# CNCMicaMini.net
KiCad netlist of a schematic drawn in Altium Designer
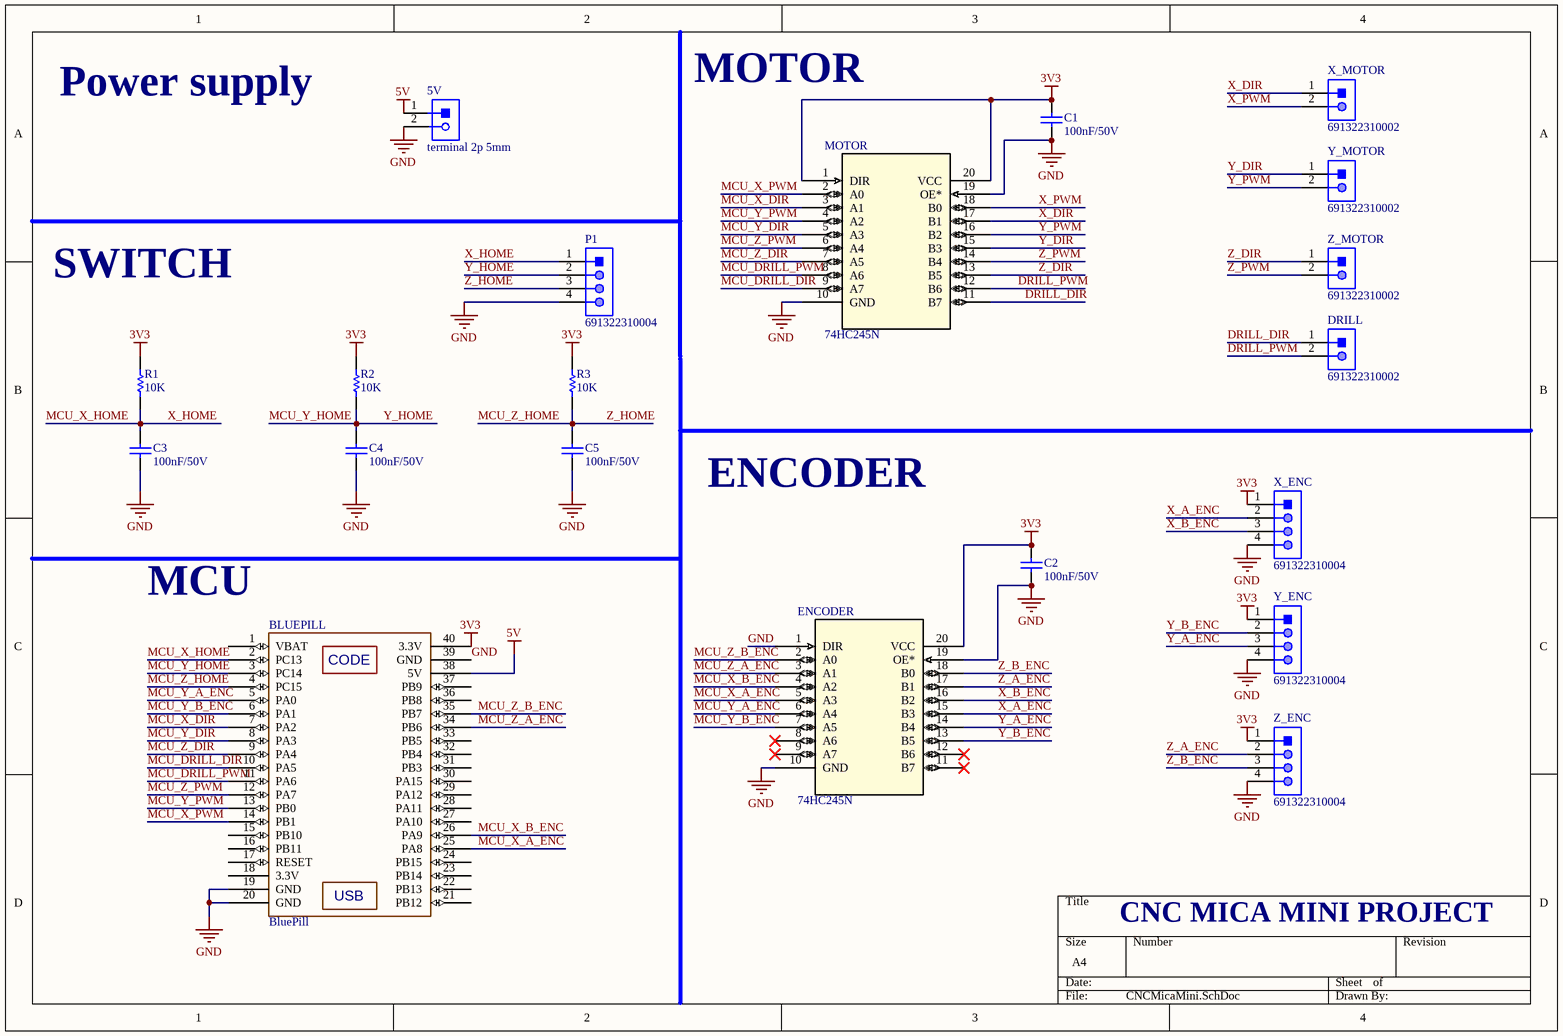
[diagram p0: CNCMicaMini.SchDoc]

(export (version "E")
  (design (tool "Eeschema 10.0.6"))
  (components
    (comp (ref "5V")
      (value "terminal 2p 5mm")
      (footprint "terminal 2p 5mm")
      (libsource (lib "CNCMicaMini") (part "terminal 2p 5mm"))
    )
    (comp (ref "BLUEPILL")
      (value "BluePill")
      (footprint "BlUEPILL")
      (libsource (lib "dev-board") (part "BluePill"))
    )
    (comp (ref "C1")
      (value "100nF/50V")
      (footprint "CAP-SM-0805")
      (description "CAP CER 0.1UF 50V Y5V 0805")
      (fields
        (field (name "MANUFACTURER") "Samsung Electro-Mechanics")
        (field (name "MANUFACTURER PART NUMBER") "CL21F104ZBCNNNC")
      )
      (libsource (lib "capacitor-smd") (part "Cap-100nF-50V-0805"))
    )
    (comp (ref "C2")
      (value "100nF/50V")
      (footprint "CAP-SM-0805")
      (description "CAP CER 0.1UF 50V Y5V 0805")
      (fields
        (field (name "MANUFACTURER") "Samsung Electro-Mechanics")
        (field (name "MANUFACTURER PART NUMBER") "CL21F104ZBCNNNC")
      )
      (libsource (lib "capacitor-smd") (part "Cap-100nF-50V-0805"))
    )
    (comp (ref "C3")
      (value "100nF/50V")
      (footprint "CAP-SM-0805")
      (description "CAP CER 0.1UF 50V Y5V 0805")
      (fields
        (field (name "MANUFACTURER") "Samsung Electro-Mechanics")
        (field (name "MANUFACTURER PART NUMBER") "CL21F104ZBCNNNC")
      )
      (libsource (lib "capacitor-smd") (part "Cap-100nF-50V-0805"))
    )
    (comp (ref "C4")
      (value "100nF/50V")
      (footprint "CAP-SM-0805")
      (description "CAP CER 0.1UF 50V Y5V 0805")
      (fields
        (field (name "MANUFACTURER") "Samsung Electro-Mechanics")
        (field (name "MANUFACTURER PART NUMBER") "CL21F104ZBCNNNC")
      )
      (libsource (lib "capacitor-smd") (part "Cap-100nF-50V-0805"))
    )
    (comp (ref "C5")
      (value "100nF/50V")
      (footprint "CAP-SM-0805")
      (description "CAP CER 0.1UF 50V Y5V 0805")
      (fields
        (field (name "MANUFACTURER") "Samsung Electro-Mechanics")
        (field (name "MANUFACTURER PART NUMBER") "CL21F104ZBCNNNC")
      )
      (libsource (lib "capacitor-smd") (part "Cap-100nF-50V-0805"))
    )
    (comp (ref "DRILL")
      (value "691322310002")
      (footprint "691322310002")
      (description "WR-TBL Serie 322 Horizontal PCB Header, Pluggable, pitch 3.81mm, 2p")
      (fields (field (name "PUBLISHER") "Wurth Elektronik"))
      (libsource (lib "WR-TBL_Pluggable PCB Header") (part "691322310002"))
    )
    (comp (ref "ENCODER")
      (value "74HC245N")
      (footprint "74HC245N")
      (description "No Description Available")
      (fields (field (name "COPYRIGHT") "Copyright (C) 2022 Ultra Librarian. All rights reserved."))
      (libsource (lib "CNCMicaMini") (part "74HC245N"))
    )
    (comp (ref "MOTOR")
      (value "74HC245N")
      (footprint "74HC245N")
      (description "No Description Available")
      (fields (field (name "COPYRIGHT") "Copyright (C) 2022 Ultra Librarian. All rights reserved."))
      (libsource (lib "CNCMicaMini") (part "74HC245N"))
    )
    (comp (ref "P1")
      (value "691322310004")
      (footprint "691322310004")
      (description "WR-TBL Serie 322 Horizontal PCB Header, Pluggable, pitch 3.81mm, 4p")
      (fields (field (name "PUBLISHER") "Wurth Elektronik"))
      (libsource (lib "WR-TBL_Pluggable PCB Header") (part "691322310004"))
    )
    (comp (ref "R1")
      (value "10K")
      (footprint "resistor-smd:RES-SM-0805")
      (description "RES 10K OHM 1% 1/4W 0805")
      (fields
        (field (name "MANUFACTURER") "Stackpole Electronics Inc")
        (field (name "MANUFACTURER PART NUMBER") "RNCP0805FTD10K0")
      )
      (libsource (lib "resistor-smd") (part "Res-10k-0805"))
    )
    (comp (ref "R2")
      (value "10K")
      (footprint "resistor-smd:RES-SM-0805")
      (description "RES 10K OHM 1% 1/4W 0805")
      (fields
        (field (name "MANUFACTURER") "Stackpole Electronics Inc")
        (field (name "MANUFACTURER PART NUMBER") "RNCP0805FTD10K0")
      )
      (libsource (lib "resistor-smd") (part "Res-10k-0805"))
    )
    (comp (ref "R3")
      (value "10K")
      (footprint "resistor-smd:RES-SM-0805")
      (description "RES 10K OHM 1% 1/4W 0805")
      (fields
        (field (name "MANUFACTURER") "Stackpole Electronics Inc")
        (field (name "MANUFACTURER PART NUMBER") "RNCP0805FTD10K0")
      )
      (libsource (lib "resistor-smd") (part "Res-10k-0805"))
    )
    (comp (ref "X_ENC")
      (value "691322310004")
      (footprint "691322310004")
      (description "WR-TBL Serie 322 Horizontal PCB Header, Pluggable, pitch 3.81mm, 4p")
      (fields (field (name "PUBLISHER") "Wurth Elektronik"))
      (libsource (lib "WR-TBL_Pluggable PCB Header") (part "691322310004"))
    )
    (comp (ref "X_MOTOR")
      (value "691322310002")
      (footprint "691322310002")
      (description "WR-TBL Serie 322 Horizontal PCB Header, Pluggable, pitch 3.81mm, 2p")
      (fields (field (name "PUBLISHER") "Wurth Elektronik"))
      (libsource (lib "WR-TBL_Pluggable PCB Header") (part "691322310002"))
    )
    (comp (ref "Y_ENC")
      (value "691322310004")
      (footprint "691322310004")
      (description "WR-TBL Serie 322 Horizontal PCB Header, Pluggable, pitch 3.81mm, 4p")
      (fields (field (name "PUBLISHER") "Wurth Elektronik"))
      (libsource (lib "WR-TBL_Pluggable PCB Header") (part "691322310004"))
    )
    (comp (ref "Y_MOTOR")
      (value "691322310002")
      (footprint "691322310002")
      (description "WR-TBL Serie 322 Horizontal PCB Header, Pluggable, pitch 3.81mm, 2p")
      (fields (field (name "PUBLISHER") "Wurth Elektronik"))
      (libsource (lib "WR-TBL_Pluggable PCB Header") (part "691322310002"))
    )
    (comp (ref "Z_ENC")
      (value "691322310004")
      (footprint "691322310004")
      (description "WR-TBL Serie 322 Horizontal PCB Header, Pluggable, pitch 3.81mm, 4p")
      (fields (field (name "PUBLISHER") "Wurth Elektronik"))
      (libsource (lib "WR-TBL_Pluggable PCB Header") (part "691322310004"))
    )
    (comp (ref "Z_MOTOR")
      (value "691322310002")
      (footprint "691322310002")
      (description "WR-TBL Serie 322 Horizontal PCB Header, Pluggable, pitch 3.81mm, 2p")
      (fields (field (name "PUBLISHER") "Wurth Elektronik"))
      (libsource (lib "WR-TBL_Pluggable PCB Header") (part "691322310002"))
    )
  )
  (nets
    (net (code "1") (name "/DRILL_DIR") (class "Default")
      (node (ref "DRILL") (pin "1") (pinfunction "1_1") (pintype "passive"))
      (node (ref "MOTOR") (pin "11") (pinfunction "B7_11") (pintype "bidirectional"))
    )
    (net (code "2") (name "/DRILL_PWM") (class "Default")
      (node (ref "DRILL") (pin "2") (pinfunction "2_2") (pintype "passive"))
      (node (ref "MOTOR") (pin "12") (pinfunction "B6_12") (pintype "bidirectional"))
    )
    (net (code "3") (name "/MCU_DRILL_DIR") (class "Default")
      (node (ref "BLUEPILL") (pin "10") (pinfunction "PA5_10") (pintype "bidirectional"))
      (node (ref "MOTOR") (pin "9") (pinfunction "A7_9") (pintype "bidirectional"))
    )
    (net (code "4") (name "/MCU_DRILL_PWM") (class "Default")
      (node (ref "BLUEPILL") (pin "11") (pinfunction "PA6_11") (pintype "bidirectional"))
      (node (ref "MOTOR") (pin "8") (pinfunction "A6_8") (pintype "bidirectional"))
    )
    (net (code "5") (name "/MCU_X_A_ENC") (class "Default")
      (node (ref "BLUEPILL") (pin "25") (pinfunction "PA8_25") (pintype "bidirectional"))
      (node (ref "ENCODER") (pin "5") (pinfunction "A3_5") (pintype "bidirectional"))
    )
    (net (code "6") (name "/MCU_X_B_ENC") (class "Default")
      (node (ref "BLUEPILL") (pin "26") (pinfunction "PA9_26") (pintype "bidirectional"))
      (node (ref "ENCODER") (pin "4") (pinfunction "A2_4") (pintype "bidirectional"))
    )
    (net (code "7") (name "/MCU_X_DIR") (class "Default")
      (node (ref "BLUEPILL") (pin "7") (pinfunction "PA2_7") (pintype "bidirectional"))
      (node (ref "MOTOR") (pin "3") (pinfunction "A1_3") (pintype "bidirectional"))
    )
    (net (code "8") (name "/MCU_X_HOME") (class "Default")
      (node (ref "BLUEPILL") (pin "2") (pinfunction "PC13_2") (pintype "bidirectional"))
      (node (ref "C3") (pin "2") (pinfunction "2_2") (pintype "passive"))
      (node (ref "P1") (pin "1") (pinfunction "1_1") (pintype "passive"))
      (node (ref "R1") (pin "1") (pinfunction "1_1") (pintype "passive"))
    )
    (net (code "9") (name "/MCU_X_PWM") (class "Default")
      (node (ref "BLUEPILL") (pin "14") (pinfunction "PB1_14") (pintype "bidirectional"))
      (node (ref "MOTOR") (pin "2") (pinfunction "A0_2") (pintype "bidirectional"))
    )
    (net (code "10") (name "/MCU_Y_A_ENC") (class "Default")
      (node (ref "BLUEPILL") (pin "5") (pinfunction "PA0_5") (pintype "bidirectional"))
      (node (ref "ENCODER") (pin "6") (pinfunction "A4_6") (pintype "bidirectional"))
    )
    (net (code "11") (name "/MCU_Y_B_ENC") (class "Default")
      (node (ref "BLUEPILL") (pin "6") (pinfunction "PA1_6") (pintype "bidirectional"))
      (node (ref "ENCODER") (pin "7") (pinfunction "A5_7") (pintype "bidirectional"))
    )
    (net (code "12") (name "/MCU_Y_DIR") (class "Default")
      (node (ref "BLUEPILL") (pin "8") (pinfunction "PA3_8") (pintype "bidirectional"))
      (node (ref "MOTOR") (pin "5") (pinfunction "A3_5") (pintype "bidirectional"))
    )
    (net (code "13") (name "/MCU_Y_HOME") (class "Default")
      (node (ref "BLUEPILL") (pin "3") (pinfunction "PC14_3") (pintype "bidirectional"))
      (node (ref "C4") (pin "2") (pinfunction "2_2") (pintype "passive"))
      (node (ref "P1") (pin "2") (pinfunction "2_2") (pintype "passive"))
      (node (ref "R2") (pin "1") (pinfunction "1_1") (pintype "passive"))
    )
    (net (code "14") (name "/MCU_Y_PWM") (class "Default")
      (node (ref "BLUEPILL") (pin "13") (pinfunction "PB0_13") (pintype "bidirectional"))
      (node (ref "MOTOR") (pin "4") (pinfunction "A2_4") (pintype "bidirectional"))
    )
    (net (code "15") (name "/MCU_Z_A_ENC") (class "Default")
      (node (ref "BLUEPILL") (pin "34") (pinfunction "PB6_34") (pintype "bidirectional"))
      (node (ref "ENCODER") (pin "3") (pinfunction "A1_3") (pintype "bidirectional"))
    )
    (net (code "16") (name "/MCU_Z_B_ENC") (class "Default")
      (node (ref "BLUEPILL") (pin "35") (pinfunction "PB7_35") (pintype "bidirectional"))
      (node (ref "ENCODER") (pin "2") (pinfunction "A0_2") (pintype "bidirectional"))
    )
    (net (code "17") (name "/MCU_Z_DIR") (class "Default")
      (node (ref "BLUEPILL") (pin "9") (pinfunction "PA4_9") (pintype "bidirectional"))
      (node (ref "MOTOR") (pin "7") (pinfunction "A5_7") (pintype "bidirectional"))
    )
    (net (code "18") (name "/MCU_Z_HOME") (class "Default")
      (node (ref "BLUEPILL") (pin "4") (pinfunction "PC15_4") (pintype "bidirectional"))
      (node (ref "C5") (pin "2") (pinfunction "2_2") (pintype "passive"))
      (node (ref "P1") (pin "3") (pinfunction "3_3") (pintype "passive"))
      (node (ref "R3") (pin "1") (pinfunction "1_1") (pintype "passive"))
    )
    (net (code "19") (name "/MCU_Z_PWM") (class "Default")
      (node (ref "BLUEPILL") (pin "12") (pinfunction "PA7_12") (pintype "bidirectional"))
      (node (ref "MOTOR") (pin "6") (pinfunction "A4_6") (pintype "bidirectional"))
    )
    (net (code "20") (name "/X_A_ENC") (class "Default")
      (node (ref "ENCODER") (pin "15") (pinfunction "B3_15") (pintype "bidirectional"))
      (node (ref "X_ENC") (pin "2") (pinfunction "2_2") (pintype "passive"))
    )
    (net (code "21") (name "/X_B_ENC") (class "Default")
      (node (ref "ENCODER") (pin "16") (pinfunction "B2_16") (pintype "bidirectional"))
      (node (ref "X_ENC") (pin "3") (pinfunction "3_3") (pintype "passive"))
    )
    (net (code "22") (name "/X_DIR") (class "Default")
      (node (ref "MOTOR") (pin "17") (pinfunction "B1_17") (pintype "bidirectional"))
      (node (ref "X_MOTOR") (pin "1") (pinfunction "1_1") (pintype "passive"))
    )
    (net (code "23") (name "/X_PWM") (class "Default")
      (node (ref "MOTOR") (pin "18") (pinfunction "B0_18") (pintype "bidirectional"))
      (node (ref "X_MOTOR") (pin "2") (pinfunction "2_2") (pintype "passive"))
    )
    (net (code "24") (name "/Y_A_ENC") (class "Default")
      (node (ref "ENCODER") (pin "14") (pinfunction "B4_14") (pintype "bidirectional"))
      (node (ref "Y_ENC") (pin "3") (pinfunction "3_3") (pintype "passive"))
    )
    (net (code "25") (name "/Y_B_ENC") (class "Default")
      (node (ref "ENCODER") (pin "13") (pinfunction "B5_13") (pintype "bidirectional"))
      (node (ref "Y_ENC") (pin "2") (pinfunction "2_2") (pintype "passive"))
    )
    (net (code "26") (name "/Y_DIR") (class "Default")
      (node (ref "MOTOR") (pin "15") (pinfunction "B3_15") (pintype "bidirectional"))
      (node (ref "Y_MOTOR") (pin "1") (pinfunction "1_1") (pintype "passive"))
    )
    (net (code "27") (name "/Y_PWM") (class "Default")
      (node (ref "MOTOR") (pin "16") (pinfunction "B2_16") (pintype "bidirectional"))
      (node (ref "Y_MOTOR") (pin "2") (pinfunction "2_2") (pintype "passive"))
    )
    (net (code "28") (name "/Z_A_ENC") (class "Default")
      (node (ref "ENCODER") (pin "17") (pinfunction "B1_17") (pintype "bidirectional"))
      (node (ref "Z_ENC") (pin "2") (pinfunction "2_2") (pintype "passive"))
    )
    (net (code "29") (name "/Z_B_ENC") (class "Default")
      (node (ref "ENCODER") (pin "18") (pinfunction "B0_18") (pintype "bidirectional"))
      (node (ref "Z_ENC") (pin "3") (pinfunction "3_3") (pintype "passive"))
    )
    (net (code "30") (name "/Z_DIR") (class "Default")
      (node (ref "MOTOR") (pin "13") (pinfunction "B5_13") (pintype "bidirectional"))
      (node (ref "Z_MOTOR") (pin "1") (pinfunction "1_1") (pintype "passive"))
    )
    (net (code "31") (name "/Z_PWM") (class "Default")
      (node (ref "MOTOR") (pin "14") (pinfunction "B4_14") (pintype "bidirectional"))
      (node (ref "Z_MOTOR") (pin "2") (pinfunction "2_2") (pintype "passive"))
    )
    (net (code "32") (name "3V3") (class "Default")
      (node (ref "BLUEPILL") (pin "40") (pinfunction "3.3V_40") (pintype "power_in"))
      (node (ref "C1") (pin "2") (pinfunction "2_2") (pintype "passive"))
      (node (ref "C2") (pin "2") (pinfunction "2_2") (pintype "passive"))
      (node (ref "ENCODER") (pin "20") (pinfunction "VCC_20") (pintype "power_in"))
      (node (ref "MOTOR") (pin "1") (pinfunction "DIR_1") (pintype "input"))
      (node (ref "MOTOR") (pin "20") (pinfunction "VCC_20") (pintype "power_in"))
      (node (ref "R1") (pin "2") (pinfunction "2_2") (pintype "passive"))
      (node (ref "R2") (pin "2") (pinfunction "2_2") (pintype "passive"))
      (node (ref "R3") (pin "2") (pinfunction "2_2") (pintype "passive"))
      (node (ref "X_ENC") (pin "1") (pinfunction "1_1") (pintype "passive"))
      (node (ref "Y_ENC") (pin "1") (pinfunction "1_1") (pintype "passive"))
      (node (ref "Z_ENC") (pin "1") (pinfunction "1_1") (pintype "passive"))
    )
    (net (code "33") (name "5V") (class "Default")
      (node (ref "5V") (pin "1") (pinfunction "1_1") (pintype "passive"))
      (node (ref "BLUEPILL") (pin "38") (pinfunction "5V_38") (pintype "power_in"))
    )
    (net (code "34") (name "GND") (class "Default")
      (node (ref "5V") (pin "2") (pinfunction "1_2") (pintype "passive"))
      (node (ref "BLUEPILL") (pin "19") (pinfunction "GND_19") (pintype "power_in"))
      (node (ref "BLUEPILL") (pin "20") (pinfunction "GND_20") (pintype "power_in"))
      (node (ref "BLUEPILL") (pin "39") (pinfunction "GND_39") (pintype "power_in"))
      (node (ref "C1") (pin "1") (pinfunction "1_1") (pintype "passive"))
      (node (ref "C2") (pin "1") (pinfunction "1_1") (pintype "passive"))
      (node (ref "C3") (pin "1") (pinfunction "1_1") (pintype "passive"))
      (node (ref "C4") (pin "1") (pinfunction "1_1") (pintype "passive"))
      (node (ref "C5") (pin "1") (pinfunction "1_1") (pintype "passive"))
      (node (ref "ENCODER") (pin "1") (pinfunction "DIR_1") (pintype "input"))
      (node (ref "ENCODER") (pin "10") (pinfunction "GND_10") (pintype "power_in"))
      (node (ref "ENCODER") (pin "19") (pinfunction "OE*_19") (pintype "input"))
      (node (ref "MOTOR") (pin "10") (pinfunction "GND_10") (pintype "power_in"))
      (node (ref "MOTOR") (pin "19") (pinfunction "OE*_19") (pintype "input"))
      (node (ref "P1") (pin "4") (pinfunction "4_4") (pintype "passive"))
      (node (ref "X_ENC") (pin "4") (pinfunction "4_4") (pintype "passive"))
      (node (ref "Y_ENC") (pin "4") (pinfunction "4_4") (pintype "passive"))
      (node (ref "Z_ENC") (pin "4") (pinfunction "4_4") (pintype "passive"))
    )
    (net (code "35") (name "unconnected-(BLUEPILL-3.3V-Pad18)") (class "Default")
      (node (ref "BLUEPILL") (pin "18") (pinfunction "3.3V_18") (pintype "power_in"))
    )
    (net (code "36") (name "unconnected-(BLUEPILL-PA10-Pad27)") (class "Default")
      (node (ref "BLUEPILL") (pin "27") (pinfunction "PA10_27") (pintype "bidirectional"))
    )
    (net (code "37") (name "unconnected-(BLUEPILL-PA11-Pad28)") (class "Default")
      (node (ref "BLUEPILL") (pin "28") (pinfunction "PA11_28") (pintype "bidirectional"))
    )
    (net (code "38") (name "unconnected-(BLUEPILL-PA12-Pad29)") (class "Default")
      (node (ref "BLUEPILL") (pin "29") (pinfunction "PA12_29") (pintype "bidirectional"))
    )
    (net (code "39") (name "unconnected-(BLUEPILL-PA15-Pad30)") (class "Default")
      (node (ref "BLUEPILL") (pin "30") (pinfunction "PA15_30") (pintype "bidirectional"))
    )
    (net (code "40") (name "unconnected-(BLUEPILL-PB3-Pad31)") (class "Default")
      (node (ref "BLUEPILL") (pin "31") (pinfunction "PB3_31") (pintype "bidirectional"))
    )
    (net (code "41") (name "unconnected-(BLUEPILL-PB4-Pad32)") (class "Default")
      (node (ref "BLUEPILL") (pin "32") (pinfunction "PB4_32") (pintype "bidirectional"))
    )
    (net (code "42") (name "unconnected-(BLUEPILL-PB5-Pad33)") (class "Default")
      (node (ref "BLUEPILL") (pin "33") (pinfunction "PB5_33") (pintype "bidirectional"))
    )
    (net (code "43") (name "unconnected-(BLUEPILL-PB8-Pad36)") (class "Default")
      (node (ref "BLUEPILL") (pin "36") (pinfunction "PB8_36") (pintype "bidirectional"))
    )
    (net (code "44") (name "unconnected-(BLUEPILL-PB9-Pad37)") (class "Default")
      (node (ref "BLUEPILL") (pin "37") (pinfunction "PB9_37") (pintype "bidirectional"))
    )
    (net (code "45") (name "unconnected-(BLUEPILL-PB10-Pad15)") (class "Default")
      (node (ref "BLUEPILL") (pin "15") (pinfunction "PB10_15") (pintype "bidirectional"))
    )
    (net (code "46") (name "unconnected-(BLUEPILL-PB11-Pad16)") (class "Default")
      (node (ref "BLUEPILL") (pin "16") (pinfunction "PB11_16") (pintype "bidirectional"))
    )
    (net (code "47") (name "unconnected-(BLUEPILL-PB12-Pad21)") (class "Default")
      (node (ref "BLUEPILL") (pin "21") (pinfunction "PB12_21") (pintype "bidirectional"))
    )
    (net (code "48") (name "unconnected-(BLUEPILL-PB13-Pad22)") (class "Default")
      (node (ref "BLUEPILL") (pin "22") (pinfunction "PB13_22") (pintype "bidirectional"))
    )
    (net (code "49") (name "unconnected-(BLUEPILL-PB14-Pad23)") (class "Default")
      (node (ref "BLUEPILL") (pin "23") (pinfunction "PB14_23") (pintype "bidirectional"))
    )
    (net (code "50") (name "unconnected-(BLUEPILL-PB15-Pad24)") (class "Default")
      (node (ref "BLUEPILL") (pin "24") (pinfunction "PB15_24") (pintype "bidirectional"))
    )
    (net (code "51") (name "unconnected-(BLUEPILL-RESET-Pad17)") (class "Default")
      (node (ref "BLUEPILL") (pin "17") (pinfunction "RESET_17") (pintype "bidirectional"))
    )
    (net (code "52") (name "unconnected-(BLUEPILL-VBAT-Pad1)") (class "Default")
      (node (ref "BLUEPILL") (pin "1") (pinfunction "VBAT_1") (pintype "bidirectional"))
    )
    (net (code "53") (name "unconnected-(ENCODER-A6-Pad8)") (class "Default")
      (node (ref "ENCODER") (pin "8") (pinfunction "A6_8") (pintype "bidirectional+no_connect"))
    )
    (net (code "54") (name "unconnected-(ENCODER-A7-Pad9)") (class "Default")
      (node (ref "ENCODER") (pin "9") (pinfunction "A7_9") (pintype "bidirectional+no_connect"))
    )
    (net (code "55") (name "unconnected-(ENCODER-B6-Pad12)") (class "Default")
      (node (ref "ENCODER") (pin "12") (pinfunction "B6_12") (pintype "bidirectional+no_connect"))
    )
    (net (code "56") (name "unconnected-(ENCODER-B7-Pad11)") (class "Default")
      (node (ref "ENCODER") (pin "11") (pinfunction "B7_11") (pintype "bidirectional+no_connect"))
    )
  )
)
